# GBxCart_RW_v1_1_Schematic.net
KiCad netlist of a schematic drawn in EAGLE
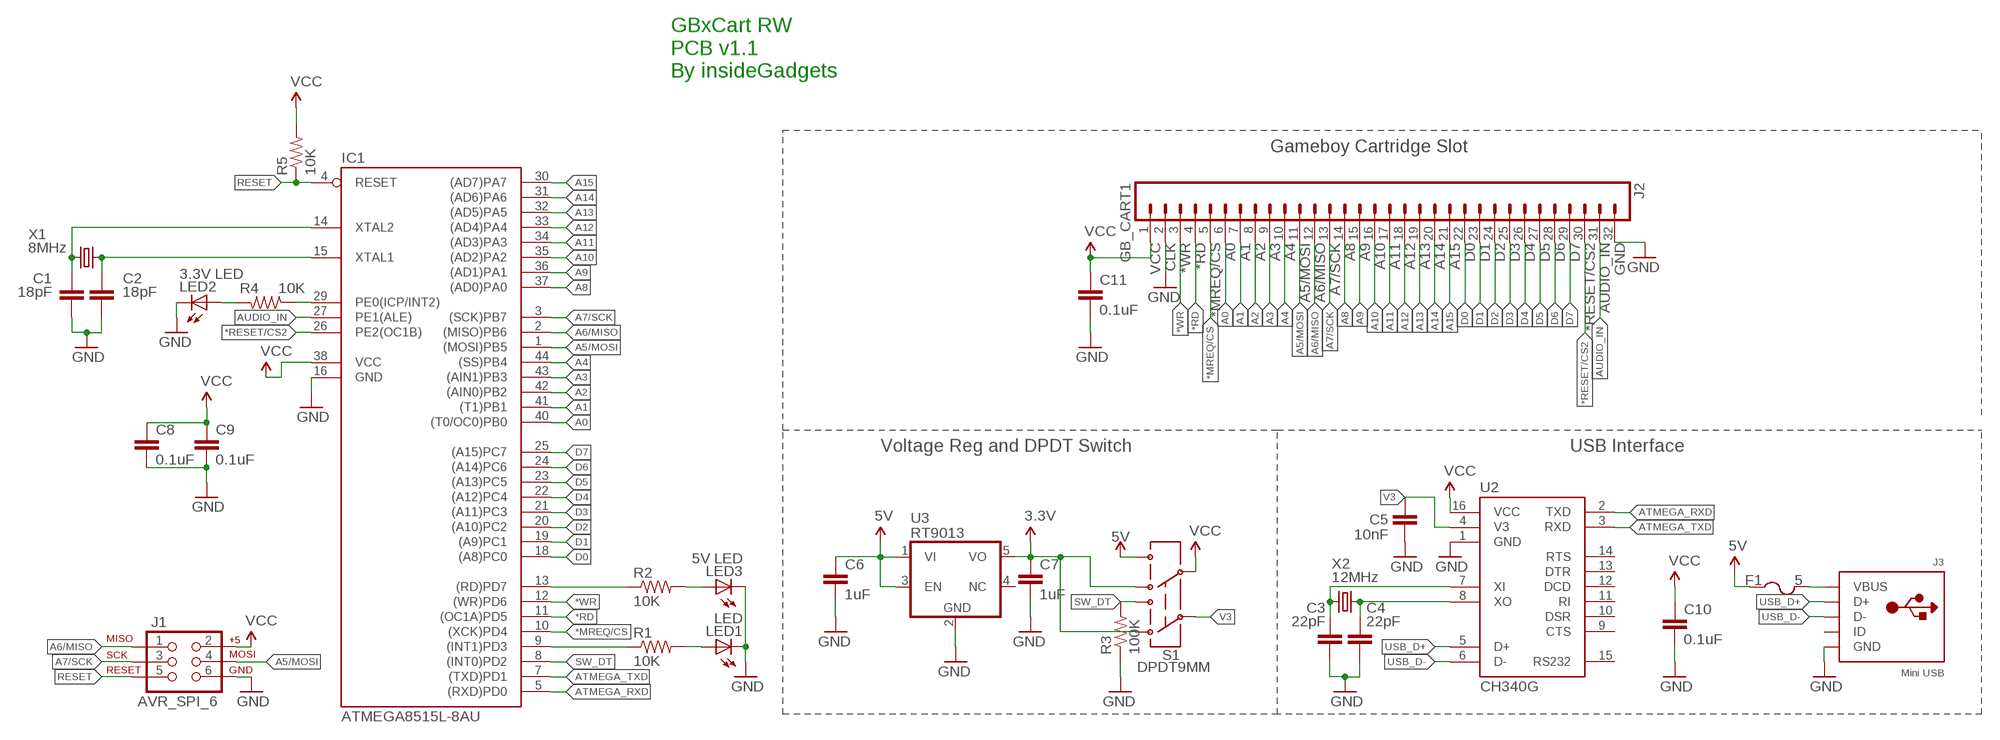
[diagram p0: schematic, sheet 1]

(export (version "E")
  (design (tool "Eeschema 10.0.6"))
  (components
    (comp (ref "C1")
      (value "18pF")
      (footprint "eagle-import:C0805K")
      (libsource (lib "eagle-import") (part "CAP0805"))
    )
    (comp (ref "C2")
      (value "18pF")
      (footprint "eagle-import:C0805K")
      (libsource (lib "eagle-import") (part "CAP0805"))
    )
    (comp (ref "C3")
      (value "22pF")
      (footprint "eagle-import:C0805K")
      (libsource (lib "eagle-import") (part "CAP0805"))
    )
    (comp (ref "C4")
      (value "22pF")
      (footprint "eagle-import:C0805K")
      (libsource (lib "eagle-import") (part "CAP0805"))
    )
    (comp (ref "C5")
      (value "10nF")
      (footprint "eagle-import:C0805K")
      (libsource (lib "eagle-import") (part "CAP0805"))
    )
    (comp (ref "C6")
      (value "1uF")
      (footprint "eagle-import:C0805K")
      (libsource (lib "eagle-import") (part "CAP0805"))
    )
    (comp (ref "C7")
      (value "1uF")
      (footprint "eagle-import:C0805K")
      (libsource (lib "eagle-import") (part "CAP0805"))
    )
    (comp (ref "C8")
      (value "0.1uF")
      (footprint "eagle-import:C0805K")
      (libsource (lib "eagle-import") (part "CAP0805"))
    )
    (comp (ref "C9")
      (value "0.1uF")
      (footprint "eagle-import:C0805K")
      (libsource (lib "eagle-import") (part "CAP0805"))
    )
    (comp (ref "C10")
      (value "0.1uF")
      (footprint "eagle-import:C0805K")
      (libsource (lib "eagle-import") (part "CAP0805"))
    )
    (comp (ref "C11")
      (value "0.1uF")
      (footprint "eagle-import:C0805K")
      (libsource (lib "eagle-import") (part "CAP0805"))
    )
    (comp (ref "F1")
      (value "5")
      (footprint "eagle-import:R1206")
      (libsource (lib "eagle-import") (part "PTCFUSE-1206"))
    )
    (comp (ref "IC1")
      (value "ATMEGA8515L-8AU")
      (footprint "eagle-import:TQFP44")
      (libsource (lib "eagle-import") (part "MEGA8515-A"))
    )
    (comp (ref "J1")
      (value "AVR_SPI_6")
      (footprint "eagle-import:2X3_2")
      (libsource (lib "eagle-import") (part "AVR_SPI_PRG_6"))
    )
    (comp (ref "J2")
      (value "GB_CART1")
      (footprint "eagle-import:GB_CART_1")
      (libsource (lib "eagle-import") (part "GB_CART1"))
    )
    (comp (ref "J3")
      (value "Mini USB")
      (footprint "eagle-import:USB-MINIB")
      (libsource (lib "eagle-import") (part "USBMINIB"))
    )
    (comp (ref "LED1")
      (value "LED")
      (footprint "eagle-import:CHIP-LED0805-NS")
      (libsource (lib "eagle-import") (part "LEDCHIP-LED0805-NS"))
    )
    (comp (ref "LED2")
      (value "3.3V LED")
      (footprint "eagle-import:CHIP-LED0805-NS")
      (libsource (lib "eagle-import") (part "LEDCHIP-LED0805-NS"))
    )
    (comp (ref "LED3")
      (value "5V LED")
      (footprint "eagle-import:CHIP-LED0805-NS")
      (libsource (lib "eagle-import") (part "LEDCHIP-LED0805-NS"))
    )
    (comp (ref "R1")
      (value "10K")
      (footprint "eagle-import:R0805_2")
      (libsource (lib "eagle-import") (part "R-US_R0805_2"))
    )
    (comp (ref "R2")
      (value "10K")
      (footprint "eagle-import:R0805_2")
      (libsource (lib "eagle-import") (part "R-US_R0805_2"))
    )
    (comp (ref "R3")
      (value "100K")
      (footprint "eagle-import:R0805_2")
      (libsource (lib "eagle-import") (part "R-US_R0805_2"))
    )
    (comp (ref "R4")
      (value "10K")
      (footprint "eagle-import:R0805_2")
      (libsource (lib "eagle-import") (part "R-US_R0805_2"))
    )
    (comp (ref "R5")
      (value "10K")
      (footprint "eagle-import:R0603")
      (libsource (lib "eagle-import") (part "R-US_R0603"))
    )
    (comp (ref "S1")
      (value "DPDT9MM")
      (footprint "eagle-import:DPDT-3")
      (libsource (lib "eagle-import") (part "SWITCH-DPDT9MM-DIP"))
    )
    (comp (ref "U2")
      (value "CH340G")
      (footprint "eagle-import:SO16")
      (libsource (lib "eagle-import") (part "CH340G"))
    )
    (comp (ref "U3")
      (value "RT9013")
      (footprint "eagle-import:SOT23-5L")
      (libsource (lib "eagle-import") (part "RT9013"))
    )
    (comp (ref "X1")
      (value "8MHz")
      (footprint "eagle-import:HC49U-V")
      (libsource (lib "eagle-import") (part "CRYSTALHC49U-V"))
    )
    (comp (ref "X2")
      (value "12MHz")
      (footprint "eagle-import:HC49U-V")
      (libsource (lib "eagle-import") (part "CRYSTALHC49U-V"))
    )
  )
  (nets
    (net (code "1") (name "*MREQ{slash}CS") (class "Default")
      (node (ref "IC1") (pin "10") (pinfunction "(XCK)PD4_10") (pintype "bidirectional"))
      (node (ref "J2") (pin "5") (pinfunction "5_5") (pintype "passive"))
    )
    (net (code "2") (name "*RD") (class "Default")
      (node (ref "IC1") (pin "11") (pinfunction "(OC1A)PD5_11") (pintype "bidirectional"))
      (node (ref "J2") (pin "4") (pinfunction "4_4") (pintype "passive"))
    )
    (net (code "3") (name "*RESET{slash}CS2") (class "Default")
      (node (ref "IC1") (pin "26") (pinfunction "PE2(OC1B)_26") (pintype "bidirectional"))
      (node (ref "J2") (pin "30") (pinfunction "30_30") (pintype "passive"))
    )
    (net (code "4") (name "*WR") (class "Default")
      (node (ref "IC1") (pin "12") (pinfunction "(WR)PD6_12") (pintype "bidirectional"))
      (node (ref "J2") (pin "3") (pinfunction "3_3") (pintype "passive"))
    )
    (net (code "5") (name "3.3V") (class "Default")
      (node (ref "C7") (pin "1") (pinfunction "1_1") (pintype "passive"))
      (node (ref "S1") (pin "1") (pinfunction "1_1") (pintype "bidirectional"))
      (node (ref "S1") (pin "4") (pinfunction "4_4") (pintype "bidirectional"))
      (node (ref "U3") (pin "5") (pinfunction "VO_5") (pintype "passive"))
    )
    (net (code "6") (name "5V") (class "Default")
      (node (ref "C6") (pin "1") (pinfunction "1_1") (pintype "passive"))
      (node (ref "F1") (pin "1") (pinfunction "1_1") (pintype "passive"))
      (node (ref "S1") (pin "6") (pinfunction "6_6") (pintype "bidirectional"))
      (node (ref "U3") (pin "1") (pinfunction "VI_1") (pintype "input"))
      (node (ref "U3") (pin "3") (pinfunction "EN_3") (pintype "input"))
    )
    (net (code "7") (name "A0") (class "Default")
      (node (ref "IC1") (pin "40") (pinfunction "(T0/OC0)PB0_40") (pintype "bidirectional"))
      (node (ref "J2") (pin "6") (pinfunction "6_6") (pintype "passive"))
    )
    (net (code "8") (name "A1") (class "Default")
      (node (ref "IC1") (pin "41") (pinfunction "(T1)PB1_41") (pintype "bidirectional"))
      (node (ref "J2") (pin "7") (pinfunction "7_7") (pintype "passive"))
    )
    (net (code "9") (name "A2") (class "Default")
      (node (ref "IC1") (pin "42") (pinfunction "(AIN0)PB2_42") (pintype "bidirectional"))
      (node (ref "J2") (pin "8") (pinfunction "8_8") (pintype "passive"))
    )
    (net (code "10") (name "A3") (class "Default")
      (node (ref "IC1") (pin "43") (pinfunction "(AIN1)PB3_43") (pintype "bidirectional"))
      (node (ref "J2") (pin "9") (pinfunction "9_9") (pintype "passive"))
    )
    (net (code "11") (name "A4") (class "Default")
      (node (ref "IC1") (pin "44") (pinfunction "(SS)PB4_44") (pintype "bidirectional"))
      (node (ref "J2") (pin "10") (pinfunction "10_10") (pintype "passive"))
    )
    (net (code "12") (name "A5{slash}MOSI") (class "Default")
      (node (ref "IC1") (pin "1") (pinfunction "(MOSI)PB5_1") (pintype "bidirectional"))
      (node (ref "J1") (pin "4") (pinfunction "4_4") (pintype "passive"))
      (node (ref "J2") (pin "11") (pinfunction "11_11") (pintype "passive"))
    )
    (net (code "13") (name "A6{slash}MISO") (class "Default")
      (node (ref "IC1") (pin "2") (pinfunction "(MISO)PB6_2") (pintype "bidirectional"))
      (node (ref "J1") (pin "1") (pinfunction "1_1") (pintype "passive"))
      (node (ref "J2") (pin "12") (pinfunction "12_12") (pintype "passive"))
    )
    (net (code "14") (name "A7{slash}SCK") (class "Default")
      (node (ref "IC1") (pin "3") (pinfunction "(SCK)PB7_3") (pintype "bidirectional"))
      (node (ref "J1") (pin "3") (pinfunction "3_3") (pintype "passive"))
      (node (ref "J2") (pin "13") (pinfunction "13_13") (pintype "passive"))
    )
    (net (code "15") (name "A8") (class "Default")
      (node (ref "IC1") (pin "37") (pinfunction "(AD0)PA0_37") (pintype "bidirectional"))
      (node (ref "J2") (pin "14") (pinfunction "14_14") (pintype "passive"))
    )
    (net (code "16") (name "A9") (class "Default")
      (node (ref "IC1") (pin "36") (pinfunction "(AD1)PA1_36") (pintype "bidirectional"))
      (node (ref "J2") (pin "15") (pinfunction "15_15") (pintype "passive"))
    )
    (net (code "17") (name "A10") (class "Default")
      (node (ref "IC1") (pin "35") (pinfunction "(AD2)PA2_35") (pintype "bidirectional"))
      (node (ref "J2") (pin "16") (pinfunction "16_16") (pintype "passive"))
    )
    (net (code "18") (name "A11") (class "Default")
      (node (ref "IC1") (pin "34") (pinfunction "(AD3)PA3_34") (pintype "bidirectional"))
      (node (ref "J2") (pin "17") (pinfunction "17_17") (pintype "passive"))
    )
    (net (code "19") (name "A12") (class "Default")
      (node (ref "IC1") (pin "33") (pinfunction "(AD4)PA4_33") (pintype "bidirectional"))
      (node (ref "J2") (pin "18") (pinfunction "18_18") (pintype "passive"))
    )
    (net (code "20") (name "A13") (class "Default")
      (node (ref "IC1") (pin "32") (pinfunction "(AD5)PA5_32") (pintype "bidirectional"))
      (node (ref "J2") (pin "19") (pinfunction "19_19") (pintype "passive"))
    )
    (net (code "21") (name "A14") (class "Default")
      (node (ref "IC1") (pin "31") (pinfunction "(AD6)PA6_31") (pintype "bidirectional"))
      (node (ref "J2") (pin "20") (pinfunction "20_20") (pintype "passive"))
    )
    (net (code "22") (name "A15") (class "Default")
      (node (ref "IC1") (pin "30") (pinfunction "(AD7)PA7_30") (pintype "bidirectional"))
      (node (ref "J2") (pin "21") (pinfunction "21_21") (pintype "passive"))
    )
    (net (code "23") (name "ATMEGA_RXD") (class "Default")
      (node (ref "IC1") (pin "5") (pinfunction "(RXD)PD0_5") (pintype "bidirectional"))
      (node (ref "U2") (pin "2") (pinfunction "TXD_2") (pintype "bidirectional"))
    )
    (net (code "24") (name "ATMEGA_TXD") (class "Default")
      (node (ref "IC1") (pin "7") (pinfunction "(TXD)PD1_7") (pintype "bidirectional"))
      (node (ref "U2") (pin "3") (pinfunction "RXD_3") (pintype "bidirectional"))
    )
    (net (code "25") (name "AUDIO_IN") (class "Default")
      (node (ref "IC1") (pin "27") (pinfunction "PE1(ALE)_27") (pintype "bidirectional"))
      (node (ref "J2") (pin "31") (pinfunction "31_31") (pintype "passive"))
    )
    (net (code "26") (name "D0") (class "Default")
      (node (ref "IC1") (pin "18") (pinfunction "(A8)PC0_18") (pintype "bidirectional"))
      (node (ref "J2") (pin "22") (pinfunction "22_22") (pintype "passive"))
    )
    (net (code "27") (name "D1") (class "Default")
      (node (ref "IC1") (pin "19") (pinfunction "(A9)PC1_19") (pintype "bidirectional"))
      (node (ref "J2") (pin "23") (pinfunction "23_23") (pintype "passive"))
    )
    (net (code "28") (name "D2") (class "Default")
      (node (ref "IC1") (pin "20") (pinfunction "(A10)PC2_20") (pintype "bidirectional"))
      (node (ref "J2") (pin "24") (pinfunction "24_24") (pintype "passive"))
    )
    (net (code "29") (name "D3") (class "Default")
      (node (ref "IC1") (pin "21") (pinfunction "(A11)PC3_21") (pintype "bidirectional"))
      (node (ref "J2") (pin "25") (pinfunction "25_25") (pintype "passive"))
    )
    (net (code "30") (name "D4") (class "Default")
      (node (ref "IC1") (pin "22") (pinfunction "(A12)PC4_22") (pintype "bidirectional"))
      (node (ref "J2") (pin "26") (pinfunction "26_26") (pintype "passive"))
    )
    (net (code "31") (name "D5") (class "Default")
      (node (ref "IC1") (pin "23") (pinfunction "(A13)PC5_23") (pintype "bidirectional"))
      (node (ref "J2") (pin "27") (pinfunction "27_27") (pintype "passive"))
    )
    (net (code "32") (name "D6") (class "Default")
      (node (ref "IC1") (pin "24") (pinfunction "(A14)PC6_24") (pintype "bidirectional"))
      (node (ref "J2") (pin "28") (pinfunction "28_28") (pintype "passive"))
    )
    (net (code "33") (name "D7") (class "Default")
      (node (ref "IC1") (pin "25") (pinfunction "(A15)PC7_25") (pintype "bidirectional"))
      (node (ref "J2") (pin "29") (pinfunction "29_29") (pintype "passive"))
    )
    (net (code "34") (name "GND") (class "Default")
      (node (ref "C1") (pin "2") (pinfunction "2_2") (pintype "passive"))
      (node (ref "C10") (pin "2") (pinfunction "2_2") (pintype "passive"))
      (node (ref "C11") (pin "2") (pinfunction "2_2") (pintype "passive"))
      (node (ref "C2") (pin "2") (pinfunction "2_2") (pintype "passive"))
      (node (ref "C3") (pin "2") (pinfunction "2_2") (pintype "passive"))
      (node (ref "C4") (pin "2") (pinfunction "2_2") (pintype "passive"))
      (node (ref "C5") (pin "2") (pinfunction "2_2") (pintype "passive"))
      (node (ref "C6") (pin "2") (pinfunction "2_2") (pintype "passive"))
      (node (ref "C7") (pin "2") (pinfunction "2_2") (pintype "passive"))
      (node (ref "C8") (pin "2") (pinfunction "2_2") (pintype "passive"))
      (node (ref "C9") (pin "2") (pinfunction "2_2") (pintype "passive"))
      (node (ref "IC1") (pin "16") (pinfunction "GND_16") (pintype "power_in"))
      (node (ref "J1") (pin "6") (pinfunction "6_6") (pintype "passive"))
      (node (ref "J2") (pin "2") (pinfunction "2_2") (pintype "passive"))
      (node (ref "J2") (pin "32") (pinfunction "32_32") (pintype "passive"))
      (node (ref "J3") (pin "GND") (pinfunction "GND_GND") (pintype "power_in"))
      (node (ref "LED1") (pin "C") (pinfunction "C_C") (pintype "passive"))
      (node (ref "LED2") (pin "C") (pinfunction "C_C") (pintype "passive"))
      (node (ref "LED3") (pin "C") (pinfunction "C_C") (pintype "passive"))
      (node (ref "R3") (pin "1") (pinfunction "1_1") (pintype "passive"))
      (node (ref "U2") (pin "1") (pinfunction "GND_1") (pintype "power_in"))
      (node (ref "U3") (pin "2") (pinfunction "GND_2") (pintype "passive"))
    )
    (net (code "35") (name "Net-(F1-Pad2)") (class "Default")
      (node (ref "F1") (pin "2") (pinfunction "2_2") (pintype "passive"))
      (node (ref "J3") (pin "VBUS") (pinfunction "VBUS_VBUS") (pintype "power_in"))
    )
    (net (code "36") (name "Net-(IC1-(INT1)PD3)") (class "Default")
      (node (ref "IC1") (pin "9") (pinfunction "(INT1)PD3_9") (pintype "bidirectional"))
      (node (ref "R1") (pin "1") (pinfunction "1_1") (pintype "passive"))
    )
    (net (code "37") (name "Net-(IC1-(RD)PD7)") (class "Default")
      (node (ref "IC1") (pin "13") (pinfunction "(RD)PD7_13") (pintype "bidirectional"))
      (node (ref "R2") (pin "1") (pinfunction "1_1") (pintype "passive"))
    )
    (net (code "38") (name "Net-(IC1-PE0(ICP{slash}INT2))") (class "Default")
      (node (ref "IC1") (pin "29") (pinfunction "PE0(ICP/INT2)_29") (pintype "bidirectional"))
      (node (ref "R4") (pin "1") (pinfunction "1_1") (pintype "passive"))
    )
    (net (code "39") (name "Net-(IC1-XTAL1)") (class "Default")
      (node (ref "C2") (pin "1") (pinfunction "1_1") (pintype "passive"))
      (node (ref "IC1") (pin "15") (pinfunction "XTAL1_15") (pintype "bidirectional"))
      (node (ref "X1") (pin "1") (pinfunction "1_1") (pintype "passive"))
    )
    (net (code "40") (name "Net-(IC1-XTAL2)") (class "Default")
      (node (ref "C1") (pin "1") (pinfunction "1_1") (pintype "passive"))
      (node (ref "IC1") (pin "14") (pinfunction "XTAL2_14") (pintype "bidirectional"))
      (node (ref "X1") (pin "2") (pinfunction "2_2") (pintype "passive"))
    )
    (net (code "41") (name "Net-(LED1-PadA)") (class "Default")
      (node (ref "LED1") (pin "A") (pinfunction "A_A") (pintype "passive"))
      (node (ref "R1") (pin "2") (pinfunction "2_2") (pintype "passive"))
    )
    (net (code "42") (name "Net-(LED2-PadA)") (class "Default")
      (node (ref "LED2") (pin "A") (pinfunction "A_A") (pintype "passive"))
      (node (ref "R4") (pin "2") (pinfunction "2_2") (pintype "passive"))
    )
    (net (code "43") (name "Net-(LED3-PadA)") (class "Default")
      (node (ref "LED3") (pin "A") (pinfunction "A_A") (pintype "passive"))
      (node (ref "R2") (pin "2") (pinfunction "2_2") (pintype "passive"))
    )
    (net (code "44") (name "Net-(U2-XI)") (class "Default")
      (node (ref "C3") (pin "1") (pinfunction "1_1") (pintype "passive"))
      (node (ref "U2") (pin "7") (pinfunction "XI_7") (pintype "bidirectional"))
      (node (ref "X2") (pin "2") (pinfunction "2_2") (pintype "passive"))
    )
    (net (code "45") (name "Net-(U2-XO)") (class "Default")
      (node (ref "C4") (pin "1") (pinfunction "1_1") (pintype "passive"))
      (node (ref "U2") (pin "8") (pinfunction "XO_8") (pintype "bidirectional"))
      (node (ref "X2") (pin "1") (pinfunction "1_1") (pintype "passive"))
    )
    (net (code "46") (name "RESET") (class "Default")
      (node (ref "IC1") (pin "4") (pinfunction "RESET_4") (pintype "input"))
      (node (ref "J1") (pin "5") (pinfunction "5_5") (pintype "passive"))
      (node (ref "R5") (pin "1") (pinfunction "1_1") (pintype "passive"))
    )
    (net (code "47") (name "SW_DT") (class "Default")
      (node (ref "IC1") (pin "8") (pinfunction "(INT0)PD2_8") (pintype "bidirectional"))
      (node (ref "R3") (pin "2") (pinfunction "2_2") (pintype "passive"))
      (node (ref "S1") (pin "3") (pinfunction "3_3") (pintype "bidirectional"))
    )
    (net (code "48") (name "USB_D+") (class "Default")
      (node (ref "J3") (pin "D+") (pinfunction "D+_D+") (pintype "bidirectional"))
      (node (ref "U2") (pin "5") (pinfunction "D+_5") (pintype "bidirectional"))
    )
    (net (code "49") (name "USB_D-") (class "Default")
      (node (ref "J3") (pin "D-") (pinfunction "D-_D-") (pintype "bidirectional"))
      (node (ref "U2") (pin "6") (pinfunction "D-_6") (pintype "bidirectional"))
    )
    (net (code "50") (name "V3") (class "Default")
      (node (ref "C5") (pin "1") (pinfunction "1_1") (pintype "passive"))
      (node (ref "S1") (pin "2") (pinfunction "2_2") (pintype "bidirectional"))
      (node (ref "U2") (pin "4") (pinfunction "V3_4") (pintype "power_in"))
    )
    (net (code "51") (name "VCC") (class "Default")
      (node (ref "C10") (pin "1") (pinfunction "1_1") (pintype "passive"))
      (node (ref "C11") (pin "1") (pinfunction "1_1") (pintype "passive"))
      (node (ref "C8") (pin "1") (pinfunction "1_1") (pintype "passive"))
      (node (ref "C9") (pin "1") (pinfunction "1_1") (pintype "passive"))
      (node (ref "IC1") (pin "38") (pinfunction "VCC_38") (pintype "power_in"))
      (node (ref "J1") (pin "2") (pinfunction "2_2") (pintype "passive"))
      (node (ref "J2") (pin "1") (pinfunction "1_1") (pintype "passive"))
      (node (ref "R5") (pin "2") (pinfunction "2_2") (pintype "passive"))
      (node (ref "S1") (pin "5") (pinfunction "5_5") (pintype "bidirectional"))
      (node (ref "U2") (pin "16") (pinfunction "VCC_16") (pintype "power_in"))
    )
    (net (code "52") (name "unconnected-(IC1-NC1-Pad6)") (class "Default")
      (node (ref "IC1") (pin "6") (pinfunction "NC1_6") (pintype "no_connect"))
    )
    (net (code "53") (name "unconnected-(IC1-NC2-Pad17)") (class "Default")
      (node (ref "IC1") (pin "17") (pinfunction "NC2_17") (pintype "no_connect"))
    )
    (net (code "54") (name "unconnected-(IC1-NC3-Pad28)") (class "Default")
      (node (ref "IC1") (pin "28") (pinfunction "NC3_28") (pintype "no_connect"))
    )
    (net (code "55") (name "unconnected-(IC1-NC4-Pad39)") (class "Default")
      (node (ref "IC1") (pin "39") (pinfunction "NC4_39") (pintype "no_connect"))
    )
    (net (code "56") (name "unconnected-(J3-PadID)") (class "Default")
      (node (ref "J3") (pin "ID") (pinfunction "ID_ID") (pintype "bidirectional"))
    )
    (net (code "57") (name "unconnected-(U2-CTS-Pad9)") (class "Default")
      (node (ref "U2") (pin "9") (pinfunction "CTS_9") (pintype "bidirectional"))
    )
    (net (code "58") (name "unconnected-(U2-DCD-Pad12)") (class "Default")
      (node (ref "U2") (pin "12") (pinfunction "DCD_12") (pintype "bidirectional"))
    )
    (net (code "59") (name "unconnected-(U2-DSR-Pad10)") (class "Default")
      (node (ref "U2") (pin "10") (pinfunction "DSR_10") (pintype "bidirectional"))
    )
    (net (code "60") (name "unconnected-(U2-DTR-Pad13)") (class "Default")
      (node (ref "U2") (pin "13") (pinfunction "DTR_13") (pintype "bidirectional"))
    )
    (net (code "61") (name "unconnected-(U2-RI-Pad11)") (class "Default")
      (node (ref "U2") (pin "11") (pinfunction "RI_11") (pintype "bidirectional"))
    )
    (net (code "62") (name "unconnected-(U2-RS232-Pad15)") (class "Default")
      (node (ref "U2") (pin "15") (pinfunction "RS232_15") (pintype "bidirectional"))
    )
    (net (code "63") (name "unconnected-(U2-RTS-Pad14)") (class "Default")
      (node (ref "U2") (pin "14") (pinfunction "RTS_14") (pintype "bidirectional"))
    )
    (net (code "64") (name "unconnected-(U3-NC-Pad4)") (class "Default")
      (node (ref "U3") (pin "4") (pinfunction "NC_4") (pintype "no_connect"))
    )
  )
)
